# EPS_Distribution_Measurements.net
KiCad netlist of a schematic drawn in Altium Designer
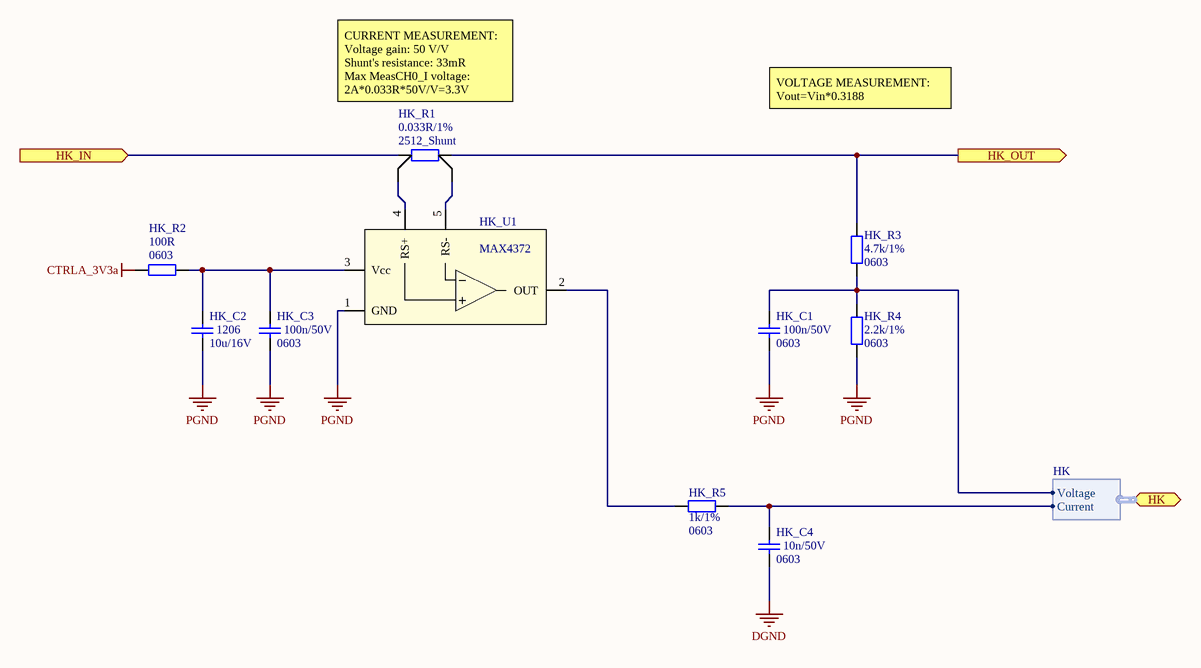
[diagram p0: EPS_Distribution_Measurements.SchDoc]

(export (version "E")
  (design (tool "Eeschema 10.0.6"))
  (components
    (comp (ref "HK_C1")
      (value "100n/50V")
      (footprint "SMD_Capacitor_0603")
      (description "Ceramic Cap Kemet COTS 100n/50V X7R 0603")
      (fields
        (field (name "MANUFACTURER") "Kemet")
        (field (name "MANUFACTURERPARTNUMBER") "C0603T104K5RALTU")
        (field (name "PACKAGE") "0603")
      )
      (libsource (lib "capacitors") (part "Cer_C0603T104K5RALTU"))
    )
    (comp (ref "HK_C2")
      (value "10u/16V")
      (footprint "SMD_Capacitor_1206")
      (description "Ceramic Cap Kemet COTS 10u/16V X7R 1206")
      (fields
        (field (name "MANUFACTURERPARTNUMBER") "C1206T106K4RACTU")
        (field (name "MANUFACTURER") "Kemet")
        (field (name "PACKGE") "1206")
      )
      (libsource (lib "capacitors") (part "Cer_C1206T106K4RACTU"))
    )
    (comp (ref "HK_C3")
      (value "100n/50V")
      (footprint "SMD_Capacitor_0603")
      (description "Ceramic Cap Kemet COTS 100n/50V X7R 0603")
      (fields
        (field (name "MANUFACTURER") "Kemet")
        (field (name "MANUFACTURERPARTNUMBER") "C0603T104K5RALTU")
        (field (name "PACKAGE") "0603")
      )
      (libsource (lib "capacitors") (part "Cer_C0603T104K5RALTU"))
    )
    (comp (ref "HK_C4")
      (value "10n/50V")
      (footprint "SMD_Capacitor_0603")
      (description "Ceramic Cap Kemet COTS 100n/50V X7R 0603")
      (fields
        (field (name "MANUFACTURER") "Kemet")
        (field (name "MANUFACTURERPARTNUMBER") "C0603T104K5RALTU")
        (field (name "PACKAGE") "0603")
      )
      (libsource (lib "capacitors") (part "Cer_C0603T104K5RALTU"))
    )
    (comp (ref "HK_R1")
      (value "0.033R/1%")
      (footprint "SMD_Resistor-shunt_2512")
      (description "33mR ,1%, 2W, shunt resistor, TE Connectivity.")
      (fields
        (field (name "MANUFACTURERPARTNUMBER") "LR2512-R033FW")
        (field (name "MANUFACTURER") "TE Connectivity")
        (field (name "PACKAGE") "2512_Shunt")
      )
      (libsource (lib "resistors") (part "LR2512-R033FW"))
    )
    (comp (ref "HK_R2")
      (value "100R")
      (footprint "SMD_Resistor_0603")
      (fields (field (name "PACKAGE") "0603"))
      (libsource (lib "resistors") (part "Res"))
    )
    (comp (ref "HK_R3")
      (value "4.7k/1%")
      (footprint "SMD_Resistor_0603")
      (fields (field (name "PACKAGE") "0603"))
      (libsource (lib "") (part "Res_1"))
    )
    (comp (ref "HK_R4")
      (value "2.2k/1%")
      (footprint "SMD_Resistor_0603")
      (fields (field (name "PACKAGE") "0603"))
      (libsource (lib "") (part "Res_1"))
    )
    (comp (ref "HK_R5")
      (value "1k/1%")
      (footprint "SMD_Resistor_0603")
      (fields (field (name "PACKAGE") "0603"))
      (libsource (lib "resistors") (part "Res"))
    )
    (comp (ref "HK_U1")
      (value "MAX4372")
      (footprint "SOT23-5")
      (description "High-Side Current-Sense Amplifier with Voltage Output")
      (fields (field (name "MANUFACTURER") "Maxim Integrated Products"))
      (libsource (lib "microcircuits") (part "MAX4372"))
    )
  )
  (nets
    (net (code "2") (name "/HK_IN") (class "Default")
      (node (ref "HK_R1") (pin "1") (pinfunction "1_1") (pintype "passive"))
    )
    (net (code "3") (name "/HK_OUT") (class "Default")
      (node (ref "HK_R1") (pin "4") (pinfunction "4_4") (pintype "passive"))
      (node (ref "HK_R3") (pin "1") (pinfunction "1_1") (pintype "passive"))
    )
    (net (code "5") (name "CTRLA_3V3a") (class "Default")
      (node (ref "HK_R2") (pin "1") (pinfunction "1_1") (pintype "passive"))
    )
    (net (code "6") (name "DGND") (class "Default")
      (node (ref "HK_C4") (pin "2") (pinfunction "2_2") (pintype "passive"))
    )
    (net (code "7") (name "Net-(HK_C1-Pad1)") (class "Default")
      (node (ref "HK_C1") (pin "1") (pinfunction "1_1") (pintype "passive"))
      (node (ref "HK_R3") (pin "2") (pinfunction "2_2") (pintype "passive"))
      (node (ref "HK_R4") (pin "1") (pinfunction "1_1") (pintype "passive"))
    )
    (net (code "8") (name "Net-(HK_C4-Pad1)") (class "Default")
      (node (ref "HK_C4") (pin "1") (pinfunction "1_1") (pintype "passive"))
      (node (ref "HK_R5") (pin "2") (pinfunction "2_2") (pintype "passive"))
    )
    (net (code "9") (name "Net-(HK_U1-OUT)") (class "Default")
      (node (ref "HK_R5") (pin "1") (pinfunction "1_1") (pintype "passive"))
      (node (ref "HK_U1") (pin "2") (pinfunction "OUT_2") (pintype "passive"))
    )
    (net (code "10") (name "Net-(HK_U1-RS+)") (class "Default")
      (node (ref "HK_R1") (pin "2") (pinfunction "2_2") (pintype "passive"))
      (node (ref "HK_U1") (pin "4") (pinfunction "RS+_4") (pintype "passive"))
    )
    (net (code "11") (name "Net-(HK_U1-RS-)") (class "Default")
      (node (ref "HK_R1") (pin "3") (pinfunction "3_3") (pintype "passive"))
      (node (ref "HK_U1") (pin "5") (pinfunction "RS-_5") (pintype "passive"))
    )
    (net (code "12") (name "Net-(HK_U1-Vcc)") (class "Default")
      (node (ref "HK_C2") (pin "1") (pinfunction "1_1") (pintype "passive"))
      (node (ref "HK_C3") (pin "1") (pinfunction "1_1") (pintype "passive"))
      (node (ref "HK_R2") (pin "2") (pinfunction "2_2") (pintype "passive"))
      (node (ref "HK_U1") (pin "3") (pinfunction "Vcc_3") (pintype "passive"))
    )
    (net (code "13") (name "PGND") (class "Default")
      (node (ref "HK_C1") (pin "2") (pinfunction "2_2") (pintype "passive"))
      (node (ref "HK_C2") (pin "2") (pinfunction "2_2") (pintype "passive"))
      (node (ref "HK_C3") (pin "2") (pinfunction "2_2") (pintype "passive"))
      (node (ref "HK_R4") (pin "2") (pinfunction "2_2") (pintype "passive"))
      (node (ref "HK_U1") (pin "1") (pinfunction "GND_1") (pintype "passive"))
    )
  )
)
